# LD_driver.net
KiCad netlist of a schematic drawn in Altium Designer
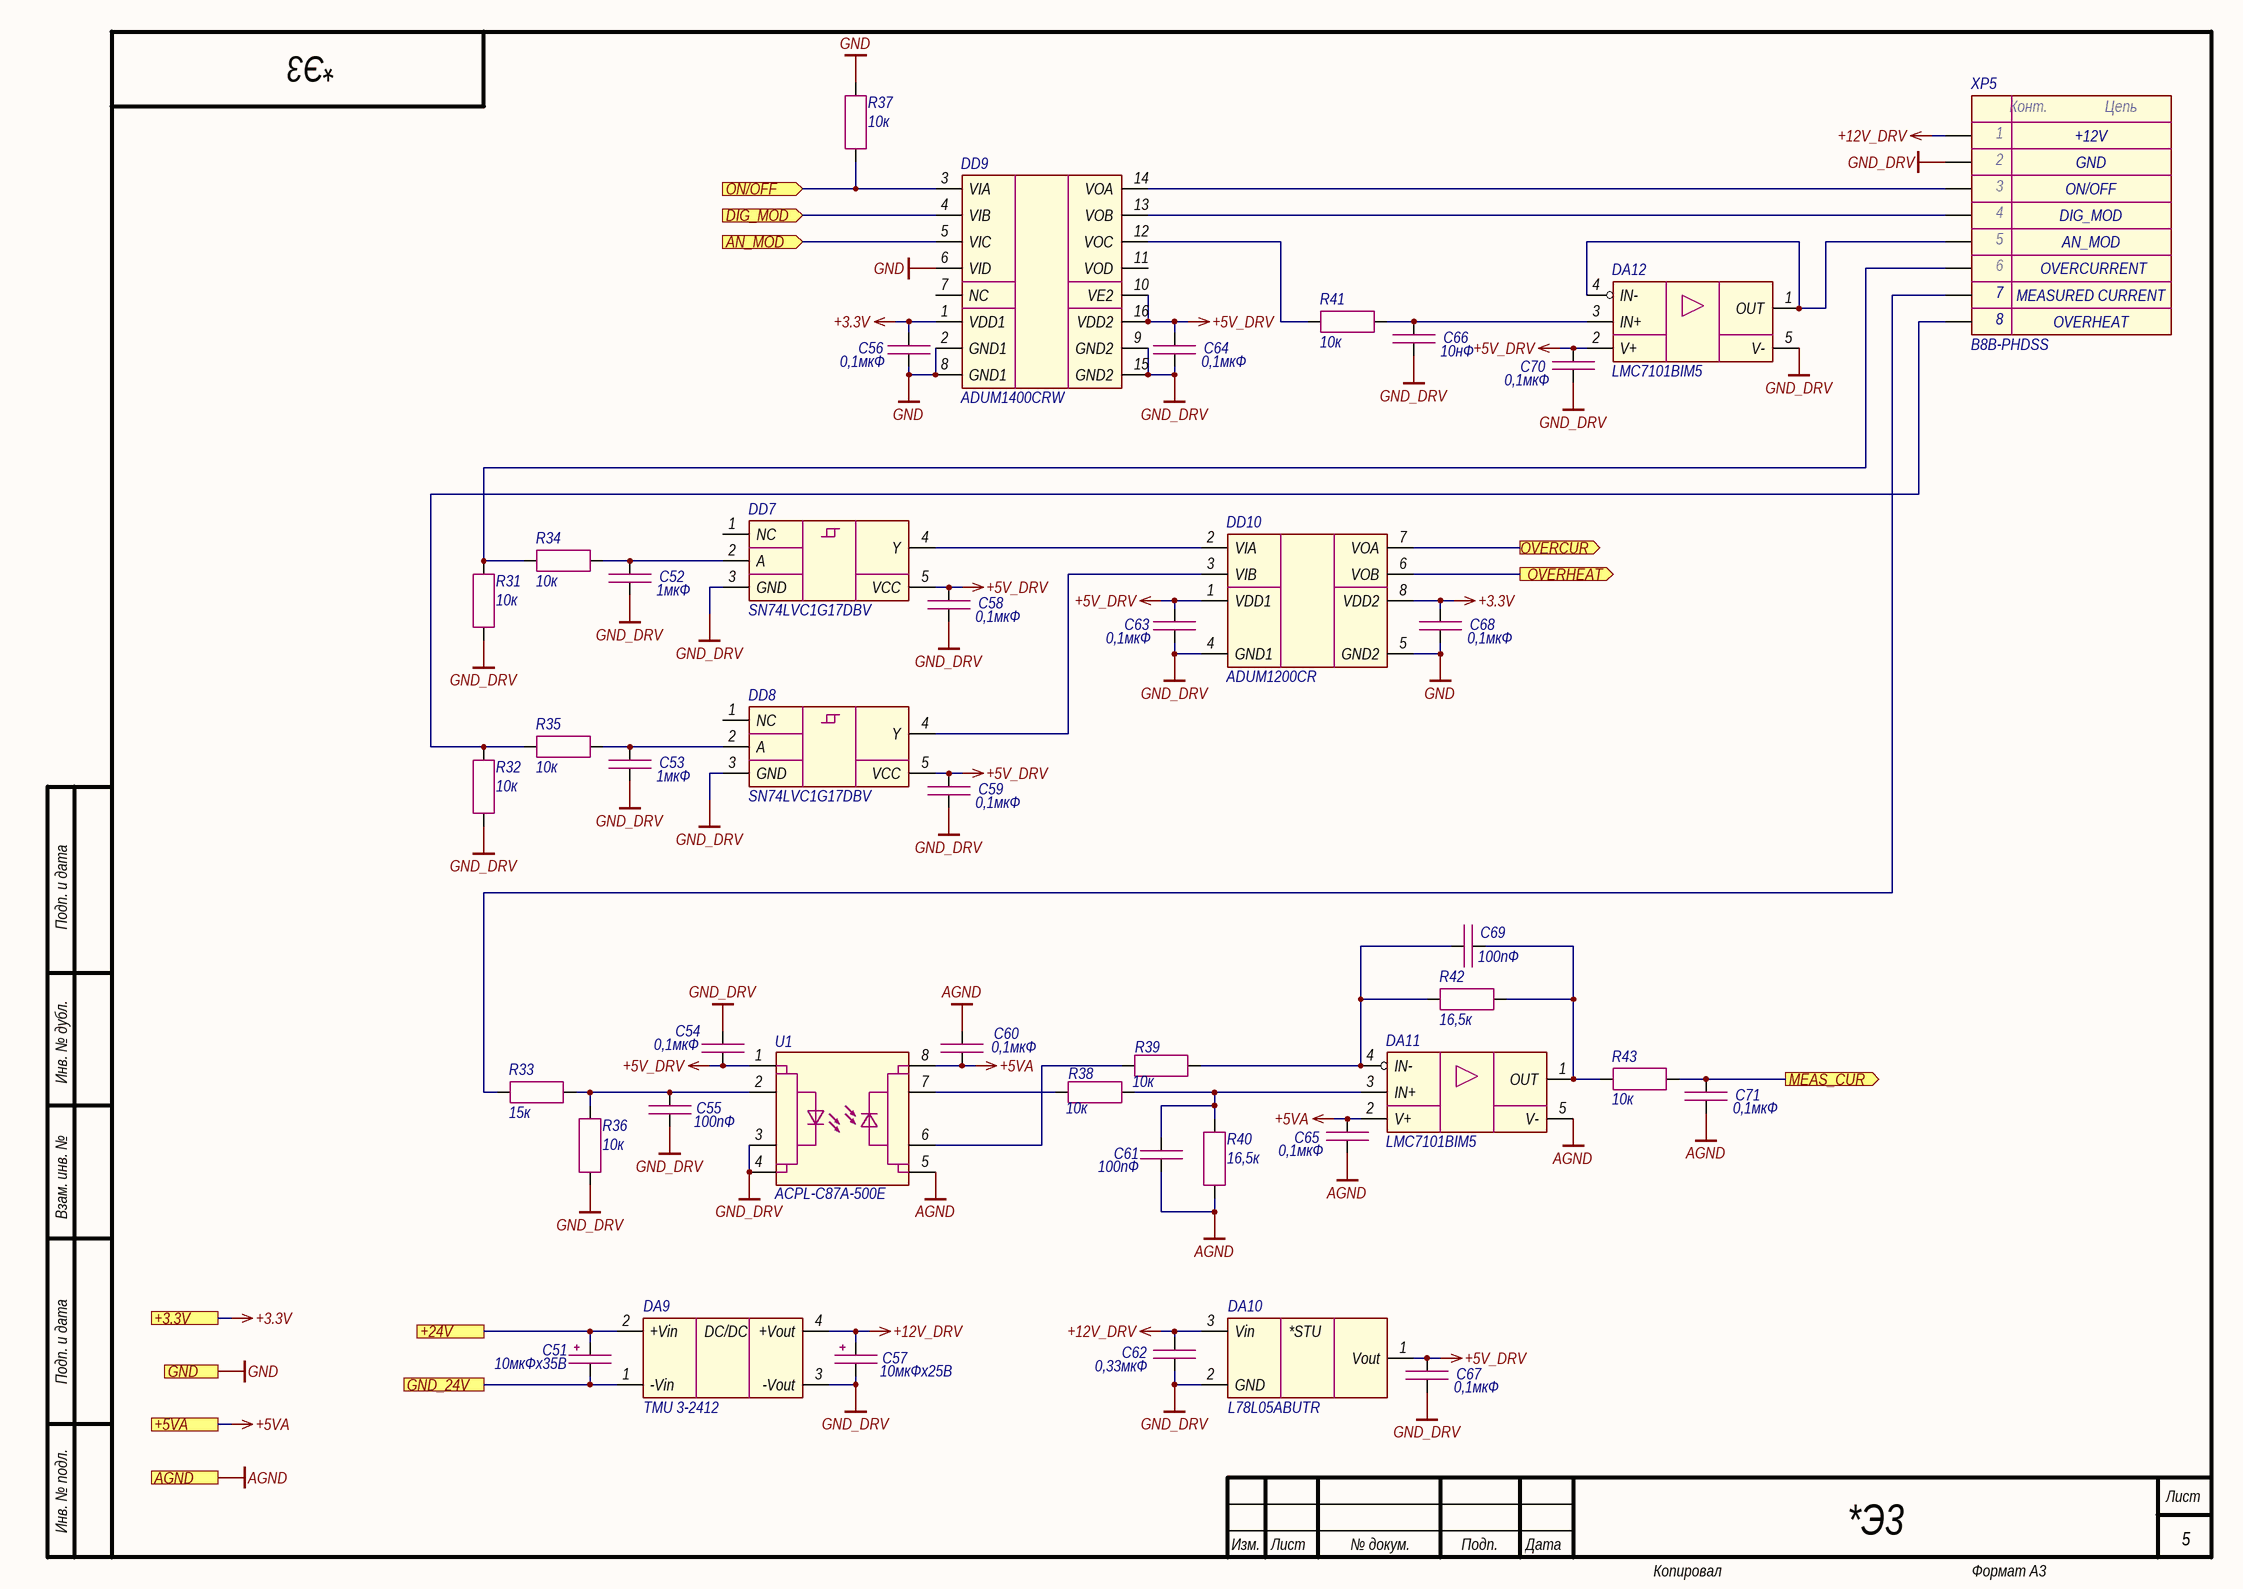
[diagram p0: LD_driver.SchDoc]

(export (version "E")
  (design (tool "Eeschema 10.0.6"))
  (components
    (comp (ref "C51")
      (value "10мкФх35B")
      (footprint "Pcb_library:CAP_C")
      (libsource (lib "Schem_library") (part "Capacitor_Polar"))
    )
    (comp (ref "C52")
      (value "1мкФ")
      (footprint "Pcb_library:CAP_0603")
      (fields (field (name "MANUFACTURER") "Murata"))
      (libsource (lib "Schem_library") (part "Capacitor"))
    )
    (comp (ref "C53")
      (value "1мкФ")
      (footprint "Pcb_library:CAP_0603")
      (fields (field (name "MANUFACTURER") "Murata"))
      (libsource (lib "Schem_library") (part "Capacitor"))
    )
    (comp (ref "C54")
      (value "0,1мкФ")
      (footprint "Pcb_library:CAP_0603")
      (fields (field (name "MANUFACTURER") "Murata"))
      (libsource (lib "Schem_library") (part "Capacitor"))
    )
    (comp (ref "C55")
      (value "100пФ")
      (footprint "Pcb_library:CAP_0603")
      (fields (field (name "MANUFACTURER") "Murata"))
      (libsource (lib "Schem_library") (part "Capacitor"))
    )
    (comp (ref "C56")
      (value "0,1мкФ")
      (footprint "Pcb_library:CAP_0603")
      (fields (field (name "MANUFACTURER") "Murata"))
      (libsource (lib "Schem_library") (part "Capacitor"))
    )
    (comp (ref "C57")
      (value "10мкФх25B")
      (footprint "Pcb_library:CAP_B")
      (libsource (lib "Schem_library") (part "Capacitor_Polar"))
    )
    (comp (ref "C58")
      (value "0,1мкФ")
      (footprint "Pcb_library:CAP_0603")
      (fields (field (name "MANUFACTURER") "Murata"))
      (libsource (lib "Schem_library") (part "Capacitor"))
    )
    (comp (ref "C59")
      (value "0,1мкФ")
      (footprint "Pcb_library:CAP_0603")
      (fields (field (name "MANUFACTURER") "Murata"))
      (libsource (lib "Schem_library") (part "Capacitor"))
    )
    (comp (ref "C60")
      (value "0,1мкФ")
      (footprint "Pcb_library:CAP_0603")
      (fields (field (name "MANUFACTURER") "Murata"))
      (libsource (lib "Schem_library") (part "Capacitor"))
    )
    (comp (ref "C61")
      (value "100пФ")
      (footprint "Pcb_library:CAP_0603")
      (fields (field (name "MANUFACTURER") "Murata"))
      (libsource (lib "Schem_library") (part "Capacitor"))
    )
    (comp (ref "C62")
      (value "0,33мкФ")
      (footprint "Pcb_library:CAP_0805")
      (fields (field (name "MANUFACTURER") "Murata"))
      (libsource (lib "Schem_library") (part "Capacitor"))
    )
    (comp (ref "C63")
      (value "0,1мкФ")
      (footprint "Pcb_library:CAP_0603")
      (fields (field (name "MANUFACTURER") "Murata"))
      (libsource (lib "Schem_library") (part "Capacitor"))
    )
    (comp (ref "C64")
      (value "0,1мкФ")
      (footprint "Pcb_library:CAP_0603")
      (fields (field (name "MANUFACTURER") "Murata"))
      (libsource (lib "Schem_library") (part "Capacitor"))
    )
    (comp (ref "C65")
      (value "0,1мкФ")
      (footprint "Pcb_library:CAP_0603")
      (fields (field (name "MANUFACTURER") "Murata"))
      (libsource (lib "Schem_library") (part "Capacitor"))
    )
    (comp (ref "C66")
      (value "10нФ")
      (footprint "Pcb_library:CAP_0603")
      (fields (field (name "MANUFACTURER") "Murata"))
      (libsource (lib "Schem_library") (part "Capacitor"))
    )
    (comp (ref "C67")
      (value "0,1мкФ")
      (footprint "Pcb_library:CAP_0603")
      (fields (field (name "MANUFACTURER") "Murata"))
      (libsource (lib "Schem_library") (part "Capacitor"))
    )
    (comp (ref "C68")
      (value "0,1мкФ")
      (footprint "Pcb_library:CAP_0603")
      (fields (field (name "MANUFACTURER") "Murata"))
      (libsource (lib "Schem_library") (part "Capacitor"))
    )
    (comp (ref "C69")
      (value "100пФ")
      (footprint "Pcb_library:CAP_0603")
      (fields (field (name "MANUFACTURER") "Murata"))
      (libsource (lib "Schem_library") (part "Capacitor"))
    )
    (comp (ref "C70")
      (value "0,1мкФ")
      (footprint "Pcb_library:CAP_0603")
      (fields (field (name "MANUFACTURER") "Murata"))
      (libsource (lib "Schem_library") (part "Capacitor"))
    )
    (comp (ref "C71")
      (value "0,1мкФ")
      (footprint "Pcb_library:CAP_0603")
      (fields (field (name "MANUFACTURER") "Murata"))
      (libsource (lib "Schem_library") (part "Capacitor"))
    )
    (comp (ref "DA9")
      (value "TMU 3-2412")
      (footprint "Pcb_library:TMU3 (SIP-4)")
      (fields (field (name "MANUFACTURER") "Traco Power"))
      (libsource (lib "Schem_library") (part "TMU3"))
    )
    (comp (ref "DA10")
      (value "L78L05ABUTR")
      (footprint "Pcb_library:SOT-89")
      (fields (field (name "MANUFACTURER") "STMicroelectronics"))
      (libsource (lib "Schem_library") (part "LD2981ABU50TR"))
    )
    (comp (ref "DA11")
      (value "LMC7101BIM5")
      (footprint "Pcb_library:SOT-23-5")
      (fields (field (name "MANUFACTURER") "Texas Instruments"))
      (libsource (lib "Schem_library") (part "LMC7101"))
    )
    (comp (ref "DA12")
      (value "LMC7101BIM5")
      (footprint "Pcb_library:SOT-23-5")
      (fields (field (name "MANUFACTURER") "Texas Instruments"))
      (libsource (lib "Schem_library") (part "LMC7101"))
    )
    (comp (ref "DD7")
      (value "SN74LVC1G17DBV")
      (footprint "Pcb_library:SOT-23-5")
      (fields (field (name "MANUFACTURER") "Texas Instruments"))
      (libsource (lib "Schem_library") (part "SN74LVC1G17"))
    )
    (comp (ref "DD8")
      (value "SN74LVC1G17DBV")
      (footprint "Pcb_library:SOT-23-5")
      (fields (field (name "MANUFACTURER") "Texas Instruments"))
      (libsource (lib "Schem_library") (part "SN74LVC1G17"))
    )
    (comp (ref "DD9")
      (value "ADUM1400CRW")
      (footprint "Pcb_library:SOIC-16W")
      (fields (field (name "MANUFACTURER") "Analog Devices"))
      (libsource (lib "Schem_library") (part "ADUM1400"))
    )
    (comp (ref "DD10")
      (value "ADUM1200CR")
      (footprint "Pcb_library:SOIC-8")
      (fields (field (name "MANUFACTURER") "Analog Devices"))
      (libsource (lib "Schem_library") (part "ADUM1200"))
    )
    (comp (ref "R31")
      (value "10к")
      (footprint "Pcb_library:RES_0603")
      (fields (field (name "MANUFACTURER") "Yageo"))
      (libsource (lib "Schem_library") (part "Resistor"))
    )
    (comp (ref "R32")
      (value "10к")
      (footprint "Pcb_library:RES_0603")
      (fields (field (name "MANUFACTURER") "Yageo"))
      (libsource (lib "Schem_library") (part "Resistor"))
    )
    (comp (ref "R33")
      (value "15к")
      (footprint "Pcb_library:RES_0603")
      (fields (field (name "MANUFACTURER") "Yageo"))
      (libsource (lib "Schem_library") (part "Resistor"))
    )
    (comp (ref "R34")
      (value "10к")
      (footprint "Pcb_library:RES_0603")
      (fields (field (name "MANUFACTURER") "Yageo"))
      (libsource (lib "Schem_library") (part "Resistor"))
    )
    (comp (ref "R35")
      (value "10к")
      (footprint "Pcb_library:RES_0603")
      (fields (field (name "MANUFACTURER") "Yageo"))
      (libsource (lib "Schem_library") (part "Resistor"))
    )
    (comp (ref "R36")
      (value "10к")
      (footprint "Pcb_library:RES_0603")
      (fields (field (name "MANUFACTURER") "Yageo"))
      (libsource (lib "Schem_library") (part "Resistor"))
    )
    (comp (ref "R37")
      (value "10к")
      (footprint "Pcb_library:RES_0603")
      (fields (field (name "MANUFACTURER") "Yageo"))
      (libsource (lib "Schem_library") (part "Resistor"))
    )
    (comp (ref "R38")
      (value "10к")
      (footprint "Pcb_library:RES_0603")
      (fields (field (name "MANUFACTURER") "Yageo"))
      (libsource (lib "Schem_library") (part "Resistor"))
    )
    (comp (ref "R39")
      (value "10к")
      (footprint "Pcb_library:RES_0603")
      (fields (field (name "MANUFACTURER") "Yageo"))
      (libsource (lib "Schem_library") (part "Resistor"))
    )
    (comp (ref "R40")
      (value "16,5к")
      (footprint "Pcb_library:RES_0603")
      (fields (field (name "MANUFACTURER") "Yageo"))
      (libsource (lib "Schem_library") (part "Resistor"))
    )
    (comp (ref "R41")
      (value "10к")
      (footprint "Pcb_library:RES_0603")
      (fields (field (name "MANUFACTURER") "Yageo"))
      (libsource (lib "Schem_library") (part "Resistor"))
    )
    (comp (ref "R42")
      (value "16,5к")
      (footprint "Pcb_library:RES_0603")
      (fields (field (name "MANUFACTURER") "Yageo"))
      (libsource (lib "Schem_library") (part "Resistor"))
    )
    (comp (ref "R43")
      (value "10к")
      (footprint "Pcb_library:RES_0603")
      (fields (field (name "MANUFACTURER") "Yageo"))
      (libsource (lib "Schem_library") (part "Resistor"))
    )
    (comp (ref "U1")
      (value "ACPL-C87A-500E")
      (footprint "Pcb_library:SSO-8")
      (fields (field (name "MANUFACTURER") "Broadcom"))
      (libsource (lib "Schem_library") (part "ACPL-C87"))
    )
    (comp (ref "XP5")
      (value "B8B-PHDSS")
      (footprint "Pcb_library:B8B-PHDSS")
      (fields (field (name "MANUFACTURER") "JST"))
      (libsource (lib "Schem_library") (part "Connector-8"))
    )
  )
  (nets
    (net (code "1") (name "+3.3V") (class "Default")
      (node (ref "C56") (pin "1") (pinfunction "1_1") (pintype "passive"))
      (node (ref "C68") (pin "1") (pinfunction "1_1") (pintype "passive"))
      (node (ref "DD10") (pin "8") (pinfunction "VDD2_8") (pintype "passive"))
      (node (ref "DD9") (pin "1") (pinfunction "VDD1_1") (pintype "passive"))
    )
    (net (code "2") (name "+5VA") (class "Default")
      (node (ref "C60") (pin "1") (pinfunction "1_1") (pintype "passive"))
      (node (ref "C65") (pin "1") (pinfunction "1_1") (pintype "passive"))
      (node (ref "DA11") (pin "2") (pinfunction "V+_2") (pintype "passive"))
      (node (ref "U1") (pin "8") (pinfunction "VDD2_8") (pintype "passive"))
    )
    (net (code "3") (name "+5V_DRV") (class "Default")
      (node (ref "C54") (pin "1") (pinfunction "1_1") (pintype "passive"))
      (node (ref "C58") (pin "1") (pinfunction "1_1") (pintype "passive"))
      (node (ref "C59") (pin "1") (pinfunction "1_1") (pintype "passive"))
      (node (ref "C63") (pin "1") (pinfunction "1_1") (pintype "passive"))
      (node (ref "C64") (pin "1") (pinfunction "1_1") (pintype "passive"))
      (node (ref "C67") (pin "1") (pinfunction "1_1") (pintype "passive"))
      (node (ref "C70") (pin "1") (pinfunction "1_1") (pintype "passive"))
      (node (ref "DA10") (pin "1") (pinfunction "Vout_1") (pintype "passive"))
      (node (ref "DA12") (pin "2") (pinfunction "V+_2") (pintype "passive"))
      (node (ref "DD10") (pin "1") (pinfunction "VDD1_1") (pintype "passive"))
      (node (ref "DD7") (pin "5") (pinfunction "VCC_5") (pintype "passive"))
      (node (ref "DD8") (pin "5") (pinfunction "VCC_5") (pintype "passive"))
      (node (ref "DD9") (pin "10") (pinfunction "VE2_10") (pintype "passive"))
      (node (ref "DD9") (pin "16") (pinfunction "VDD2_16") (pintype "passive"))
      (node (ref "U1") (pin "1") (pinfunction "VDD1_1") (pintype "passive"))
    )
    (net (code "4") (name "+12V_DRV") (class "Default")
      (node (ref "C57") (pin "1") (pinfunction "1_1") (pintype "passive"))
      (node (ref "C62") (pin "2") (pinfunction "2_2") (pintype "passive"))
      (node (ref "DA10") (pin "3") (pinfunction "Vin_3") (pintype "passive"))
      (node (ref "DA9") (pin "4") (pinfunction "+Vout_4") (pintype "passive"))
      (node (ref "XP5") (pin "1") (pintype "passive"))
    )
    (net (code "5") (name "/+24V") (class "Default")
      (node (ref "C51") (pin "1") (pinfunction "1_1") (pintype "passive"))
      (node (ref "DA9") (pin "2") (pinfunction "+Vin_2") (pintype "passive"))
    )
    (net (code "6") (name "/AN_MOD") (class "Default")
      (node (ref "DD9") (pin "5") (pinfunction "VIC_5") (pintype "passive"))
    )
    (net (code "7") (name "/DIG_MOD") (class "Default")
      (node (ref "DD9") (pin "4") (pinfunction "VIB_4") (pintype "passive"))
    )
    (net (code "8") (name "/GND_24V") (class "Default")
      (node (ref "C51") (pin "2") (pinfunction "2_2") (pintype "passive"))
      (node (ref "DA9") (pin "1") (pinfunction "-Vin_1") (pintype "passive"))
    )
    (net (code "9") (name "/MEAS_CUR") (class "Default")
      (node (ref "C71") (pin "1") (pinfunction "1_1") (pintype "passive"))
      (node (ref "R43") (pin "2") (pinfunction "2_2") (pintype "passive"))
    )
    (net (code "10") (name "/ON{slash}OFF") (class "Default")
      (node (ref "DD9") (pin "3") (pinfunction "VIA_3") (pintype "passive"))
      (node (ref "R37") (pin "2") (pinfunction "2_2") (pintype "passive"))
    )
    (net (code "11") (name "/OVERCUR") (class "Default")
      (node (ref "DD10") (pin "7") (pinfunction "VOA_7") (pintype "passive"))
    )
    (net (code "12") (name "/OVERHEAT") (class "Default")
      (node (ref "DD10") (pin "6") (pinfunction "VOB_6") (pintype "passive"))
    )
    (net (code "13") (name "AGND") (class "Default")
      (node (ref "C60") (pin "2") (pinfunction "2_2") (pintype "passive"))
      (node (ref "C61") (pin "2") (pinfunction "2_2") (pintype "passive"))
      (node (ref "C65") (pin "2") (pinfunction "2_2") (pintype "passive"))
      (node (ref "C71") (pin "2") (pinfunction "2_2") (pintype "passive"))
      (node (ref "DA11") (pin "5") (pinfunction "V-_5") (pintype "passive"))
      (node (ref "R40") (pin "2") (pinfunction "2_2") (pintype "passive"))
      (node (ref "U1") (pin "5") (pinfunction "GND2_5") (pintype "passive"))
    )
    (net (code "14") (name "GND") (class "Default")
      (node (ref "C56") (pin "2") (pinfunction "2_2") (pintype "passive"))
      (node (ref "C68") (pin "2") (pinfunction "2_2") (pintype "passive"))
      (node (ref "DD10") (pin "5") (pinfunction "GND2_5") (pintype "passive"))
      (node (ref "DD9") (pin "2") (pinfunction "GND1_2") (pintype "passive"))
      (node (ref "DD9") (pin "6") (pinfunction "VID_6") (pintype "passive"))
      (node (ref "DD9") (pin "8") (pinfunction "GND1_8") (pintype "passive"))
      (node (ref "R37") (pin "1") (pinfunction "1_1") (pintype "passive"))
    )
    (net (code "15") (name "GND_DRV") (class "Default")
      (node (ref "C52") (pin "2") (pinfunction "2_2") (pintype "passive"))
      (node (ref "C53") (pin "2") (pinfunction "2_2") (pintype "passive"))
      (node (ref "C54") (pin "2") (pinfunction "2_2") (pintype "passive"))
      (node (ref "C55") (pin "1") (pinfunction "1_1") (pintype "passive"))
      (node (ref "C57") (pin "2") (pinfunction "2_2") (pintype "passive"))
      (node (ref "C58") (pin "2") (pinfunction "2_2") (pintype "passive"))
      (node (ref "C59") (pin "2") (pinfunction "2_2") (pintype "passive"))
      (node (ref "C62") (pin "1") (pinfunction "1_1") (pintype "passive"))
      (node (ref "C63") (pin "2") (pinfunction "2_2") (pintype "passive"))
      (node (ref "C64") (pin "2") (pinfunction "2_2") (pintype "passive"))
      (node (ref "C66") (pin "2") (pinfunction "2_2") (pintype "passive"))
      (node (ref "C67") (pin "2") (pinfunction "2_2") (pintype "passive"))
      (node (ref "C70") (pin "2") (pinfunction "2_2") (pintype "passive"))
      (node (ref "DA10") (pin "2") (pinfunction "GND_2") (pintype "passive"))
      (node (ref "DA12") (pin "5") (pinfunction "V-_5") (pintype "passive"))
      (node (ref "DA9") (pin "3") (pinfunction "-Vout_3") (pintype "passive"))
      (node (ref "DD10") (pin "4") (pinfunction "GND1_4") (pintype "passive"))
      (node (ref "DD7") (pin "3") (pinfunction "GND_3") (pintype "passive"))
      (node (ref "DD8") (pin "3") (pinfunction "GND_3") (pintype "passive"))
      (node (ref "DD9") (pin "15") (pinfunction "GND2_15") (pintype "passive"))
      (node (ref "DD9") (pin "9") (pinfunction "GND2_9") (pintype "passive"))
      (node (ref "R31") (pin "1") (pinfunction "1_1") (pintype "passive"))
      (node (ref "R32") (pin "1") (pinfunction "1_1") (pintype "passive"))
      (node (ref "R36") (pin "2") (pinfunction "2_2") (pintype "passive"))
      (node (ref "U1") (pin "3") (pinfunction "SHDN_3") (pintype "passive"))
      (node (ref "U1") (pin "4") (pinfunction "GND1_4") (pintype "passive"))
      (node (ref "XP5") (pin "2") (pintype "passive"))
    )
    (net (code "16") (name "Net-(DA11-IN+)") (class "Default")
      (node (ref "C61") (pin "1") (pinfunction "1_1") (pintype "passive"))
      (node (ref "DA11") (pin "3") (pinfunction "IN+_3") (pintype "passive"))
      (node (ref "R38") (pin "2") (pinfunction "2_2") (pintype "passive"))
      (node (ref "R40") (pin "1") (pinfunction "1_1") (pintype "passive"))
    )
    (net (code "17") (name "Net-(DA11-IN-)") (class "Default")
      (node (ref "C69") (pin "1") (pinfunction "1_1") (pintype "passive"))
      (node (ref "DA11") (pin "4") (pinfunction "IN-_4") (pintype "passive"))
      (node (ref "R39") (pin "2") (pinfunction "2_2") (pintype "passive"))
      (node (ref "R42") (pin "2") (pinfunction "2_2") (pintype "passive"))
    )
    (net (code "18") (name "Net-(DA11-OUT)") (class "Default")
      (node (ref "C69") (pin "2") (pinfunction "2_2") (pintype "passive"))
      (node (ref "DA11") (pin "1") (pinfunction "OUT_1") (pintype "passive"))
      (node (ref "R42") (pin "1") (pinfunction "1_1") (pintype "passive"))
      (node (ref "R43") (pin "1") (pinfunction "1_1") (pintype "passive"))
    )
    (net (code "19") (name "Net-(DA12-IN+)") (class "Default")
      (node (ref "C66") (pin "1") (pinfunction "1_1") (pintype "passive"))
      (node (ref "DA12") (pin "3") (pinfunction "IN+_3") (pintype "passive"))
      (node (ref "R41") (pin "2") (pinfunction "2_2") (pintype "passive"))
    )
    (net (code "20") (name "Net-(DA12-IN-)") (class "Default")
      (node (ref "DA12") (pin "1") (pinfunction "OUT_1") (pintype "passive"))
      (node (ref "DA12") (pin "4") (pinfunction "IN-_4") (pintype "passive"))
      (node (ref "XP5") (pin "5") (pintype "passive"))
    )
    (net (code "21") (name "Net-(DD7-A)") (class "Default")
      (node (ref "C52") (pin "1") (pinfunction "1_1") (pintype "passive"))
      (node (ref "DD7") (pin "2") (pinfunction "A_2") (pintype "passive"))
      (node (ref "R34") (pin "2") (pinfunction "2_2") (pintype "passive"))
    )
    (net (code "22") (name "Net-(DD8-A)") (class "Default")
      (node (ref "C53") (pin "1") (pinfunction "1_1") (pintype "passive"))
      (node (ref "DD8") (pin "2") (pinfunction "A_2") (pintype "passive"))
      (node (ref "R35") (pin "2") (pinfunction "2_2") (pintype "passive"))
    )
    (net (code "23") (name "Net-(DD9-VOA)") (class "Default")
      (node (ref "DD9") (pin "14") (pinfunction "VOA_14") (pintype "passive"))
      (node (ref "XP5") (pin "3") (pintype "passive"))
    )
    (net (code "24") (name "Net-(DD9-VOB)") (class "Default")
      (node (ref "DD9") (pin "13") (pinfunction "VOB_13") (pintype "passive"))
      (node (ref "XP5") (pin "4") (pintype "passive"))
    )
    (net (code "25") (name "Net-(DD9-VOC)") (class "Default")
      (node (ref "DD9") (pin "12") (pinfunction "VOC_12") (pintype "passive"))
      (node (ref "R41") (pin "1") (pinfunction "1_1") (pintype "passive"))
    )
    (net (code "26") (name "Net-(DD10-VIA)") (class "Default")
      (node (ref "DD10") (pin "2") (pinfunction "VIA_2") (pintype "passive"))
      (node (ref "DD7") (pin "4") (pinfunction "Y_4") (pintype "passive"))
    )
    (net (code "27") (name "Net-(DD10-VIB)") (class "Default")
      (node (ref "DD10") (pin "3") (pinfunction "VIB_3") (pintype "passive"))
      (node (ref "DD8") (pin "4") (pinfunction "Y_4") (pintype "passive"))
    )
    (net (code "28") (name "Net-(R31-Pad2)") (class "Default")
      (node (ref "R31") (pin "2") (pinfunction "2_2") (pintype "passive"))
      (node (ref "R34") (pin "1") (pinfunction "1_1") (pintype "passive"))
      (node (ref "XP5") (pin "6") (pintype "passive"))
    )
    (net (code "29") (name "Net-(R32-Pad2)") (class "Default")
      (node (ref "R32") (pin "2") (pinfunction "2_2") (pintype "passive"))
      (node (ref "R35") (pin "1") (pinfunction "1_1") (pintype "passive"))
      (node (ref "XP5") (pin "8") (pintype "passive"))
    )
    (net (code "30") (name "Net-(R33-Pad2)") (class "Default")
      (node (ref "R33") (pin "2") (pinfunction "2_2") (pintype "passive"))
      (node (ref "XP5") (pin "7") (pintype "passive"))
    )
    (net (code "31") (name "Net-(U1-VIN)") (class "Default")
      (node (ref "C55") (pin "2") (pinfunction "2_2") (pintype "passive"))
      (node (ref "R33") (pin "1") (pinfunction "1_1") (pintype "passive"))
      (node (ref "R36") (pin "1") (pinfunction "1_1") (pintype "passive"))
      (node (ref "U1") (pin "2") (pinfunction "VIN_2") (pintype "passive"))
    )
    (net (code "32") (name "Net-(U1-VOUT+)") (class "Default")
      (node (ref "R38") (pin "1") (pinfunction "1_1") (pintype "passive"))
      (node (ref "U1") (pin "7") (pinfunction "VOUT+_7") (pintype "passive"))
    )
    (net (code "33") (name "Net-(U1-VOUT-)") (class "Default")
      (node (ref "R39") (pin "1") (pinfunction "1_1") (pintype "passive"))
      (node (ref "U1") (pin "6") (pinfunction "VOUT-_6") (pintype "passive"))
    )
    (net (code "34") (name "unconnected-(DD7-NC-Pad1)") (class "Default")
      (node (ref "DD7") (pin "1") (pinfunction "NC_1") (pintype "passive"))
    )
    (net (code "35") (name "unconnected-(DD8-NC-Pad1)") (class "Default")
      (node (ref "DD8") (pin "1") (pinfunction "NC_1") (pintype "passive"))
    )
    (net (code "36") (name "unconnected-(DD9-NC-Pad7)") (class "Default")
      (node (ref "DD9") (pin "7") (pinfunction "NC_7") (pintype "passive"))
    )
    (net (code "37") (name "unconnected-(DD9-VOD-Pad11)") (class "Default")
      (node (ref "DD9") (pin "11") (pinfunction "VOD_11") (pintype "passive"))
    )
  )
)
